# WT108_SIPO.net
KiCad netlist of a schematic drawn in Altium Designer
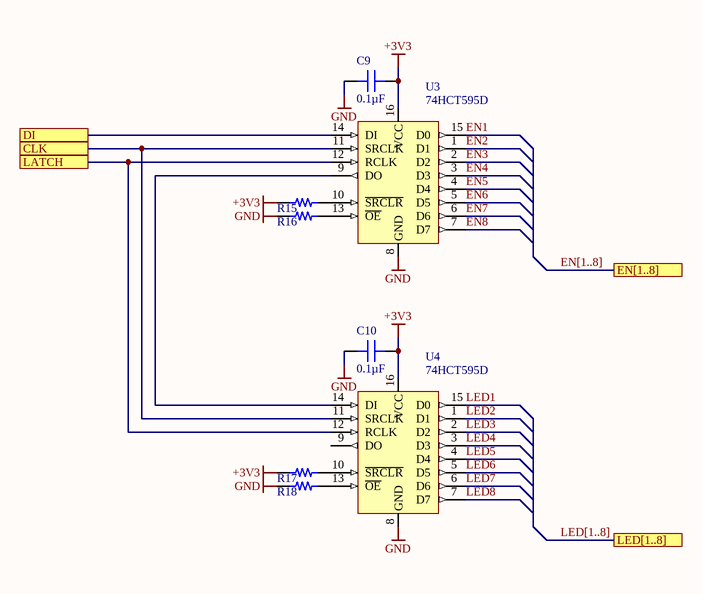
[diagram p0: WT108_SIPO.schdoc]

(export (version "E")
  (design (tool "Eeschema 10.0.6"))
  (components
    (comp (ref "C9")
      (value "0.1µF")
      (footprint "CAP 0603_1608")
      (description "CAP CER 0.1UF 50V X7R 0603")
      (fields (field (name "MANUFACTURER") "KEMET") (field (name "PART NUMBER") "C0603C104K5RAC7411"))
      (libsource (lib "Celestial Altium Library") (part "Capacitor"))
    )
    (comp (ref "C10")
      (value "0.1µF")
      (footprint "CAP 0603_1608")
      (description "CAP CER 0.1UF 50V X7R 0603")
      (fields (field (name "MANUFACTURER") "KEMET") (field (name "PART NUMBER") "C0603C104K5RAC7411"))
      (libsource (lib "Celestial Altium Library") (part "Capacitor"))
    )
    (comp (ref "R15")
      (value "10 kOhms")
      (footprint "RES 0603_1608")
      (description "RES SMD 10K OHM 0.5% 1/10W 0603")
      (fields (field (name "MANUFACTURER") "Yageo") (field (name "PART NUMBER") "RT0603DRD0710KL"))
      (libsource (lib "Celestial Altium Library") (part "Resistor"))
    )
    (comp (ref "R16")
      (value "10 kOhms")
      (footprint "RES 0603_1608")
      (description "RES SMD 10K OHM 0.5% 1/10W 0603")
      (fields (field (name "MANUFACTURER") "Yageo") (field (name "PART NUMBER") "RT0603DRD0710KL"))
      (libsource (lib "Celestial Altium Library") (part "Resistor"))
    )
    (comp (ref "R17")
      (value "10 kOhms")
      (footprint "RES 0603_1608")
      (description "RES SMD 10K OHM 0.5% 1/10W 0603")
      (fields (field (name "MANUFACTURER") "Yageo") (field (name "PART NUMBER") "RT0603DRD0710KL"))
      (libsource (lib "Celestial Altium Library") (part "Resistor"))
    )
    (comp (ref "R18")
      (value "10 kOhms")
      (footprint "RES 0603_1608")
      (description "RES SMD 10K OHM 0.5% 1/10W 0603")
      (fields (field (name "MANUFACTURER") "Yageo") (field (name "PART NUMBER") "RT0603DRD0710KL"))
      (libsource (lib "Celestial Altium Library") (part "Resistor"))
    )
    (comp (ref "U3")
      (value "74HCT595D")
      (footprint "SOP65P780X180-16N")
      (description "8-Bit Serial-Input Parallel-Output")
      (libsource (lib "7c7_IntegratedCircuits") (part "74HCT595D"))
    )
    (comp (ref "U4")
      (value "74HCT595D")
      (footprint "SOP65P780X180-16N")
      (description "8-Bit Serial-Input Parallel-Output")
      (libsource (lib "7c7_IntegratedCircuits") (part "74HCT595D"))
    )
  )
  (nets
    (net (code "1") (name "+3V3") (class "Default")
      (node (ref "C10") (pin "1") (pinfunction "1_1") (pintype "passive"))
      (node (ref "C9") (pin "1") (pinfunction "1_1") (pintype "passive"))
      (node (ref "R15") (pin "1") (pinfunction "1_1") (pintype "passive"))
      (node (ref "R17") (pin "1") (pinfunction "1_1") (pintype "passive"))
      (node (ref "U3") (pin "16") (pinfunction "VCC_16") (pintype "power_in"))
      (node (ref "U4") (pin "16") (pinfunction "VCC_16") (pintype "power_in"))
    )
    (net (code "2") (name "/CLK") (class "Default")
      (node (ref "U3") (pin "11") (pinfunction "SRCLK_11") (pintype "input"))
      (node (ref "U4") (pin "11") (pinfunction "SRCLK_11") (pintype "input"))
    )
    (net (code "3") (name "/DI") (class "Default")
      (node (ref "U3") (pin "14") (pinfunction "DI_14") (pintype "input"))
    )
    (net (code "4") (name "/EN1") (class "Default")
      (node (ref "U3") (pin "15") (pinfunction "D0_15") (pintype "output"))
    )
    (net (code "5") (name "/EN2") (class "Default")
      (node (ref "U3") (pin "1") (pinfunction "D1_1") (pintype "output"))
    )
    (net (code "6") (name "/EN3") (class "Default")
      (node (ref "U3") (pin "2") (pinfunction "D2_2") (pintype "output"))
    )
    (net (code "7") (name "/EN4") (class "Default")
      (node (ref "U3") (pin "3") (pinfunction "D3_3") (pintype "output"))
    )
    (net (code "8") (name "/EN5") (class "Default")
      (node (ref "U3") (pin "4") (pinfunction "D4_4") (pintype "output"))
    )
    (net (code "9") (name "/EN6") (class "Default")
      (node (ref "U3") (pin "5") (pinfunction "D5_5") (pintype "output"))
    )
    (net (code "10") (name "/EN7") (class "Default")
      (node (ref "U3") (pin "6") (pinfunction "D6_6") (pintype "output"))
    )
    (net (code "11") (name "/EN8") (class "Default")
      (node (ref "U3") (pin "7") (pinfunction "D7_7") (pintype "output"))
    )
    (net (code "13") (name "/LATCH") (class "Default")
      (node (ref "U3") (pin "12") (pinfunction "RCLK_12") (pintype "input"))
      (node (ref "U4") (pin "12") (pinfunction "RCLK_12") (pintype "input"))
    )
    (net (code "14") (name "/LED1") (class "Default")
      (node (ref "U4") (pin "15") (pinfunction "D0_15") (pintype "output"))
    )
    (net (code "15") (name "/LED2") (class "Default")
      (node (ref "U4") (pin "1") (pinfunction "D1_1") (pintype "output"))
    )
    (net (code "16") (name "/LED3") (class "Default")
      (node (ref "U4") (pin "2") (pinfunction "D2_2") (pintype "output"))
    )
    (net (code "17") (name "/LED4") (class "Default")
      (node (ref "U4") (pin "3") (pinfunction "D3_3") (pintype "output"))
    )
    (net (code "18") (name "/LED5") (class "Default")
      (node (ref "U4") (pin "4") (pinfunction "D4_4") (pintype "output"))
    )
    (net (code "19") (name "/LED6") (class "Default")
      (node (ref "U4") (pin "5") (pinfunction "D5_5") (pintype "output"))
    )
    (net (code "20") (name "/LED7") (class "Default")
      (node (ref "U4") (pin "6") (pinfunction "D6_6") (pintype "output"))
    )
    (net (code "21") (name "/LED8") (class "Default")
      (node (ref "U4") (pin "7") (pinfunction "D7_7") (pintype "output"))
    )
    (net (code "23") (name "GND") (class "Default")
      (node (ref "C10") (pin "2") (pinfunction "2_2") (pintype "passive"))
      (node (ref "C9") (pin "2") (pinfunction "2_2") (pintype "passive"))
      (node (ref "R16") (pin "1") (pinfunction "1_1") (pintype "passive"))
      (node (ref "R18") (pin "1") (pinfunction "1_1") (pintype "passive"))
      (node (ref "U3") (pin "8") (pinfunction "GND_8") (pintype "power_in"))
      (node (ref "U4") (pin "8") (pinfunction "GND_8") (pintype "power_in"))
    )
    (net (code "24") (name "Net-(U3-DO)") (class "Default")
      (node (ref "U3") (pin "9") (pinfunction "DO_9") (pintype "output"))
      (node (ref "U4") (pin "14") (pinfunction "DI_14") (pintype "input"))
    )
    (net (code "25") (name "Net-(U3-~{OE})") (class "Default")
      (node (ref "R16") (pin "2") (pinfunction "2_2") (pintype "passive"))
      (node (ref "U3") (pin "13") (pinfunction "~{OE}_13") (pintype "input"))
    )
    (net (code "26") (name "Net-(U3-~{SRCLR})") (class "Default")
      (node (ref "R15") (pin "2") (pinfunction "2_2") (pintype "passive"))
      (node (ref "U3") (pin "10") (pinfunction "~{SRCLR}_10") (pintype "input"))
    )
    (net (code "27") (name "Net-(U4-~{OE})") (class "Default")
      (node (ref "R18") (pin "2") (pinfunction "2_2") (pintype "passive"))
      (node (ref "U4") (pin "13") (pinfunction "~{OE}_13") (pintype "input"))
    )
    (net (code "28") (name "Net-(U4-~{SRCLR})") (class "Default")
      (node (ref "R17") (pin "2") (pinfunction "2_2") (pintype "passive"))
      (node (ref "U4") (pin "10") (pinfunction "~{SRCLR}_10") (pintype "input"))
    )
    (net (code "29") (name "unconnected-(U4-DO-Pad9)") (class "Default")
      (node (ref "U4") (pin "9") (pinfunction "DO_9") (pintype "output"))
    )
  )
)
